# Audio.net
KiCad netlist of a schematic drawn in Altium Designer
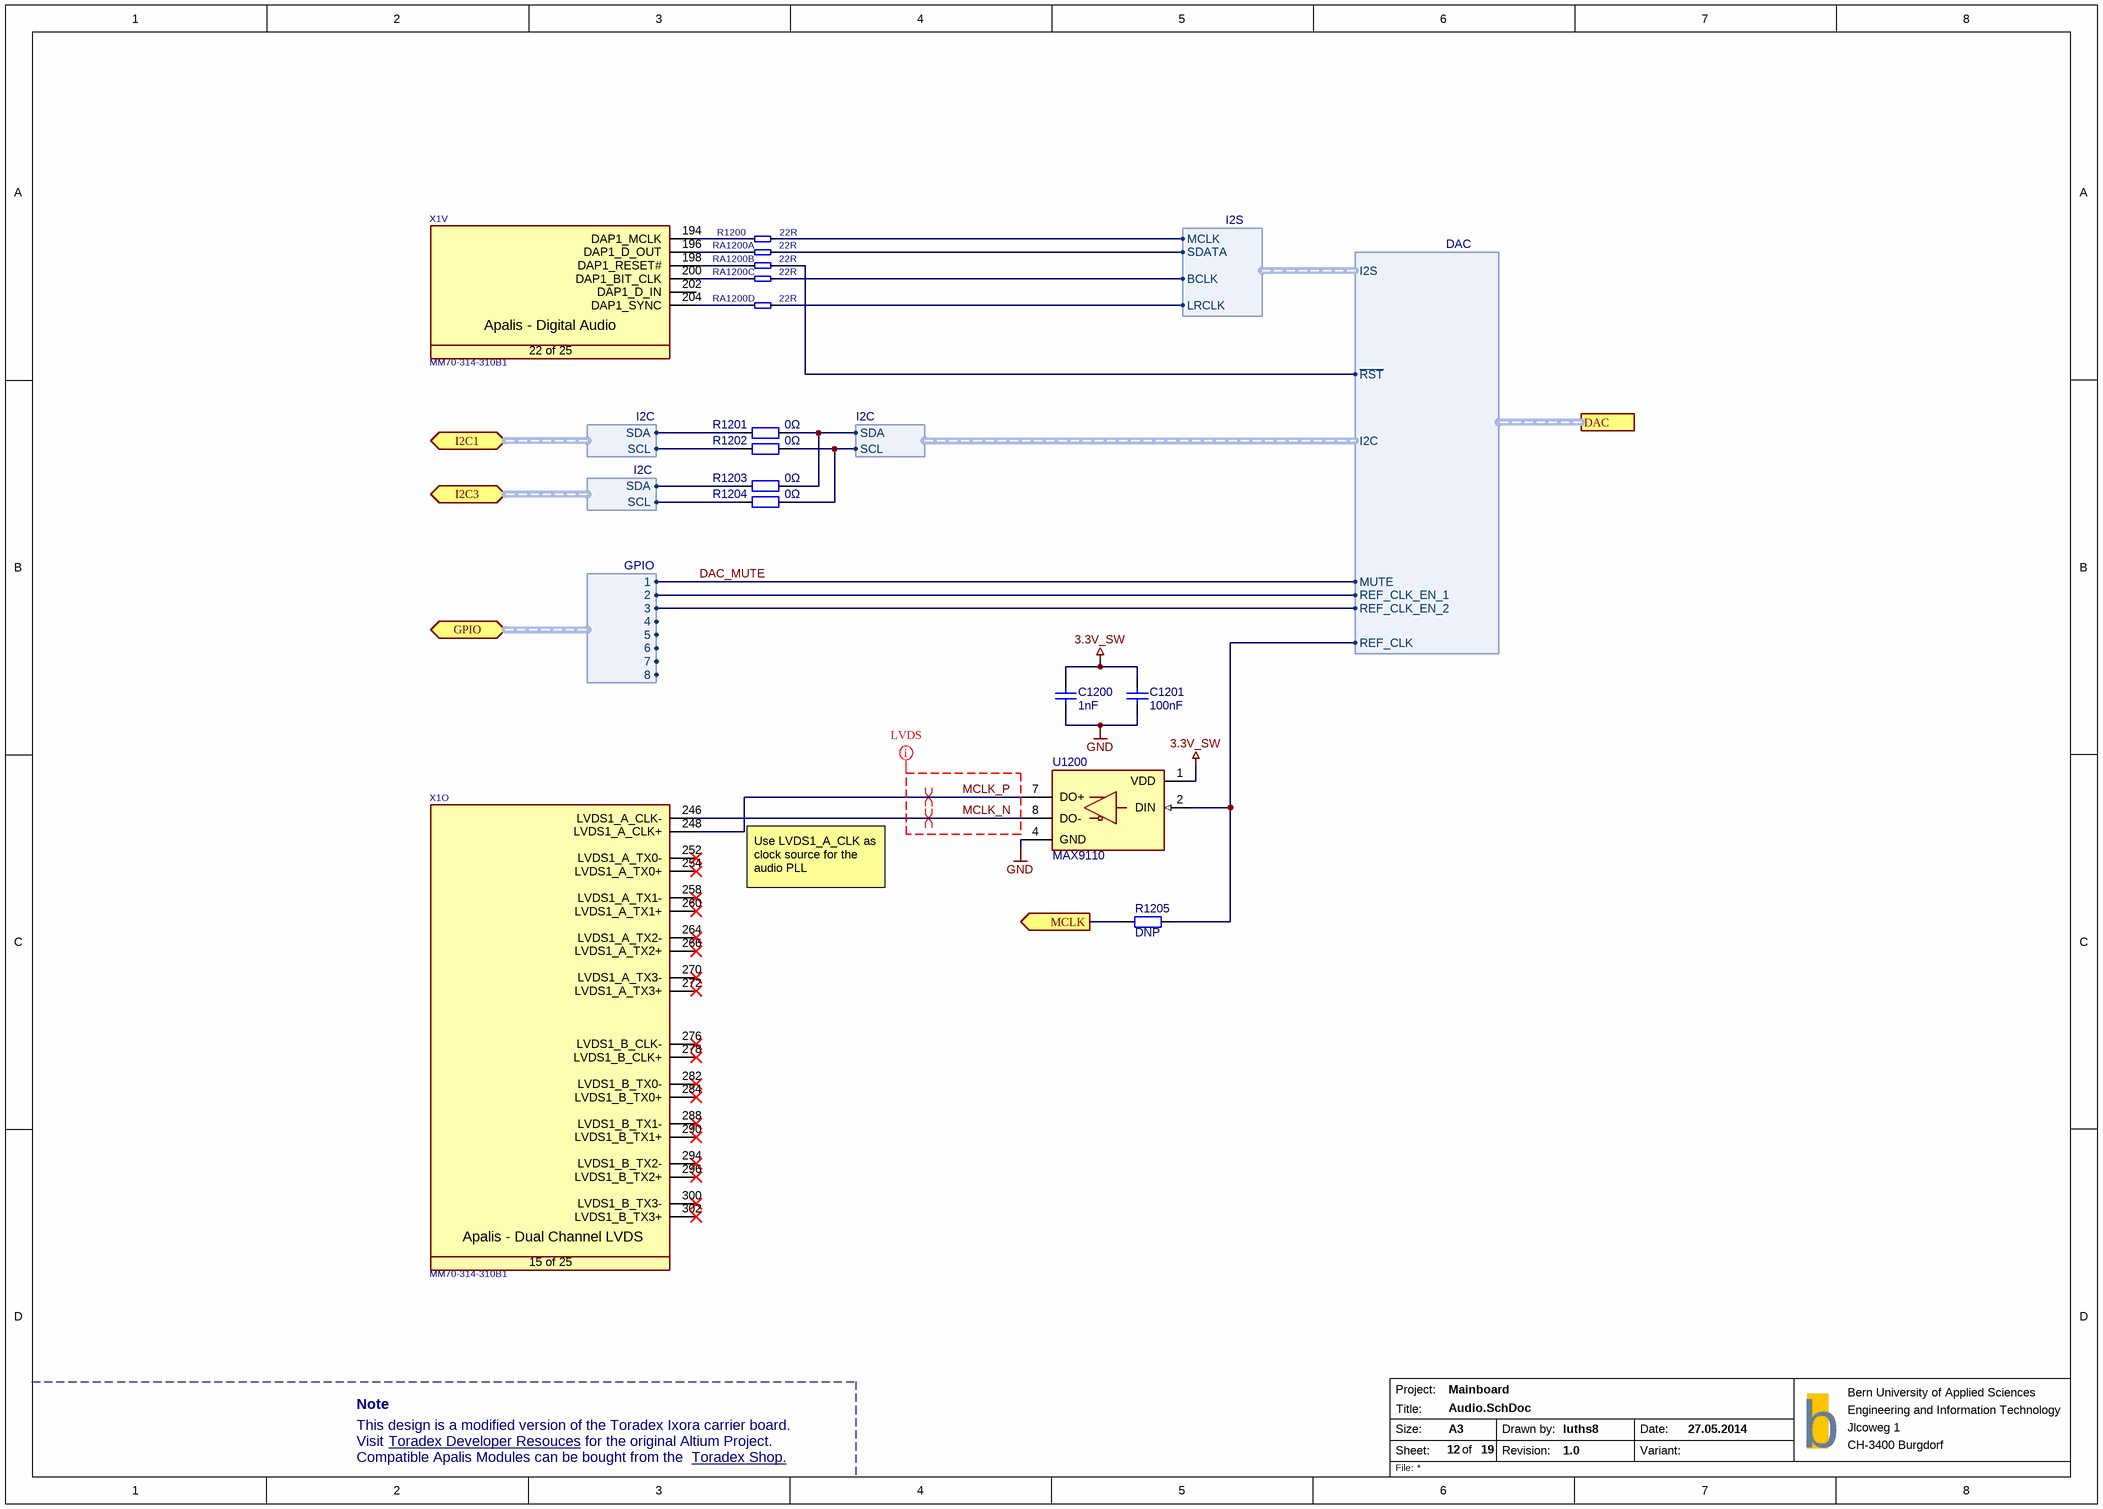
[diagram p0: Audio.SchDoc]

(export (version "E")
  (design (tool "Eeschema 10.0.6"))
  (components
    (comp (ref "C1200")
      (value "1nF")
      (footprint "SMD0603CAP")
      (description "Ceramic Capacitor")
      (libsource (lib "Audio-Streamer") (part "Capacitor Ceramic"))
    )
    (comp (ref "C1201")
      (value "100nF")
      (footprint "SMD0603CAP")
      (description "Ceramic Capacitor")
      (libsource (lib "Audio-Streamer") (part "Capacitor Ceramic"))
    )
    (comp (ref "R1200")
      (value "22R")
      (footprint "SMD0603RES")
      (description "Resistor 22 ohm 63mW 5% 0603")
      (fields (field (name "TOLERANCE") "5%"))
      (libsource (lib "Ixora") (part "R-22R-63mW-5%-0402"))
    )
    (comp (ref "R1201")
      (value "0Ω")
      (footprint "SMD0603RES")
      (description "Resistor")
      (libsource (lib "") (part "Resistor_1"))
    )
    (comp (ref "R1202")
      (value "0Ω")
      (footprint "SMD0603RES")
      (description "Resistor")
      (libsource (lib "") (part "Resistor_1"))
    )
    (comp (ref "R1203")
      (value "0Ω")
      (footprint "SMD0603RES")
      (description "Resistor")
      (libsource (lib "") (part "Resistor_1"))
    )
    (comp (ref "R1204")
      (value "0Ω")
      (footprint "SMD0603RES")
      (description "Resistor")
      (libsource (lib "") (part "Resistor_1"))
    )
    (comp (ref "R1205")
      (value "DNP")
      (footprint "SMD0603RES")
      (description "Resistor")
      (libsource (lib "Audio-Streamer") (part "Resistor"))
    )
    (comp (ref "RA1200")
      (value "22R")
      (footprint "T_Resistor_Array_X4")
      (description "Resistor Array 22 R 63mW 5% 1206")
      (fields (field (name "TOLERANCE") "5%"))
      (libsource (lib "Ixora") (part "RA-22R-63mW-5%-1206-div"))
    )
    (comp (ref "U1200")
      (value "MAX9110")
      (footprint "SOIC8")
      (description "LVDS Transmitter")
      (fields (field (name "MANUFACTURER PART NO.") "MAX9110ESA+"))
      (libsource (lib "Audio-Streamer") (part "MAX9110"))
    )
    (comp (ref "X1")
      (value "CON-JAE-MM70-314-310B1-314-0.5mm")
      (footprint "T_JAE_MM70-314-310B1")
      (description "MXM3 Connector")
      (fields (field (name "MANUFACTURER PART NO.") "MM70-314-310B1"))
      (libsource (lib "Ixora") (part "CON-JAE-MM70-314-310B1-314-0.5mm"))
    )
  )
  (nets
    (net (code "7") (name "/BCLK") (class "Default")
      (node (ref "RA1200") (pin "7") (pinfunction "7_7") (pintype "passive"))
    )
    (net (code "9") (name "/LRCLK") (class "Default")
      (node (ref "RA1200") (pin "8") (pinfunction "8_8") (pintype "passive"))
    )
    (net (code "10") (name "/MCLK") (class "Default")
      (node (ref "R1205") (pin "2") (pinfunction "2_2") (pintype "passive"))
    )
    (net (code "11") (name "/MCLK_N") (class "Default")
      (node (ref "U1200") (pin "8") (pinfunction "DO-_8") (pintype "passive"))
      (node (ref "X1") (pin "246") (pinfunction "LVDS1_A_CLK-_246") (pintype "passive"))
    )
    (net (code "12") (name "/MCLK_P") (class "Default")
      (node (ref "U1200") (pin "7") (pinfunction "DO+_7") (pintype "passive"))
      (node (ref "X1") (pin "248") (pinfunction "LVDS1_A_CLK+_248") (pintype "passive"))
    )
    (net (code "13") (name "/REF_CLK") (class "Default")
      (node (ref "R1205") (pin "1") (pinfunction "1_1") (pintype "passive"))
      (node (ref "U1200") (pin "2") (pinfunction "DIN_2") (pintype "input"))
    )
    (net (code "14") (name "/SDATA") (class "Default")
      (node (ref "RA1200") (pin "5") (pinfunction "5_5") (pintype "passive"))
    )
    (net (code "19") (name "/~{RST}") (class "Default")
      (node (ref "RA1200") (pin "6") (pinfunction "6_6") (pintype "passive"))
    )
    (net (code "20") (name "3.3V_SW") (class "Default")
      (node (ref "C1200") (pin "1") (pinfunction "1_1") (pintype "passive"))
      (node (ref "C1201") (pin "1") (pinfunction "1_1") (pintype "passive"))
      (node (ref "U1200") (pin "1") (pinfunction "VDD_1") (pintype "power_in"))
    )
    (net (code "21") (name "GND") (class "Default")
      (node (ref "C1200") (pin "2") (pinfunction "q_2") (pintype "passive"))
      (node (ref "C1201") (pin "2") (pinfunction "q_2") (pintype "passive"))
      (node (ref "U1200") (pin "4") (pinfunction "GND_4") (pintype "power_in"))
    )
    (net (code "22") (name "Net-(R1201-Pad1)") (class "Default")
      (node (ref "R1201") (pin "1") (pinfunction "1_1") (pintype "passive"))
      (node (ref "R1203") (pin "1") (pinfunction "1_1") (pintype "passive"))
    )
    (net (code "23") (name "Net-(R1202-Pad1)") (class "Default")
      (node (ref "R1202") (pin "1") (pinfunction "1_1") (pintype "passive"))
      (node (ref "R1204") (pin "1") (pinfunction "1_1") (pintype "passive"))
    )
    (net (code "24") (name "Net-(X1V-DAP1_BIT_CLK)") (class "Default")
      (node (ref "RA1200") (pin "3") (pinfunction "3_3") (pintype "passive"))
      (node (ref "X1") (pin "200") (pinfunction "DAP1_BIT_CLK_200") (pintype "passive"))
    )
    (net (code "25") (name "Net-(X1V-DAP1_D_OUT)") (class "Default")
      (node (ref "RA1200") (pin "1") (pinfunction "1_1") (pintype "passive"))
      (node (ref "X1") (pin "196") (pinfunction "DAP1_D_OUT_196") (pintype "passive"))
    )
    (net (code "26") (name "Net-(X1V-DAP1_MCLK)") (class "Default")
      (node (ref "R1200") (pin "1") (pinfunction "1_1") (pintype "passive"))
      (node (ref "X1") (pin "194") (pinfunction "DAP1_MCLK_194") (pintype "passive"))
    )
    (net (code "27") (name "Net-(X1V-DAP1_RESET#)") (class "Default")
      (node (ref "RA1200") (pin "2") (pinfunction "2_2") (pintype "passive"))
      (node (ref "X1") (pin "198") (pinfunction "DAP1_RESET#_198") (pintype "passive"))
    )
    (net (code "28") (name "Net-(X1V-DAP1_SYNC)") (class "Default")
      (node (ref "RA1200") (pin "4") (pinfunction "4_4") (pintype "passive"))
      (node (ref "X1") (pin "204") (pinfunction "DAP1_SYNC_204") (pintype "passive"))
    )
    (net (code "29") (name "unconnected-(R1200-Pad2)") (class "Default")
      (node (ref "R1200") (pin "2") (pinfunction "2_2") (pintype "passive"))
    )
    (net (code "30") (name "unconnected-(R1201-Pad2)") (class "Default")
      (node (ref "R1201") (pin "2") (pinfunction "2_2") (pintype "passive"))
    )
    (net (code "31") (name "unconnected-(R1202-Pad2)") (class "Default")
      (node (ref "R1202") (pin "2") (pinfunction "2_2") (pintype "passive"))
    )
    (net (code "32") (name "unconnected-(R1203-Pad2)") (class "Default")
      (node (ref "R1203") (pin "2") (pinfunction "2_2") (pintype "passive"))
    )
    (net (code "33") (name "unconnected-(R1204-Pad2)") (class "Default")
      (node (ref "R1204") (pin "2") (pinfunction "2_2") (pintype "passive"))
    )
    (net (code "34") (name "unconnected-(X1O-LVDS1_A_TX0+-Pad254)") (class "Default")
      (node (ref "X1") (pin "254") (pinfunction "LVDS1_A_TX0+_254") (pintype "passive+no_connect"))
    )
    (net (code "35") (name "unconnected-(X1O-LVDS1_A_TX0--Pad252)") (class "Default")
      (node (ref "X1") (pin "252") (pinfunction "LVDS1_A_TX0-_252") (pintype "passive+no_connect"))
    )
    (net (code "36") (name "unconnected-(X1O-LVDS1_A_TX1+-Pad260)") (class "Default")
      (node (ref "X1") (pin "260") (pinfunction "LVDS1_A_TX1+_260") (pintype "passive+no_connect"))
    )
    (net (code "37") (name "unconnected-(X1O-LVDS1_A_TX1--Pad258)") (class "Default")
      (node (ref "X1") (pin "258") (pinfunction "LVDS1_A_TX1-_258") (pintype "passive+no_connect"))
    )
    (net (code "38") (name "unconnected-(X1O-LVDS1_A_TX2+-Pad266)") (class "Default")
      (node (ref "X1") (pin "266") (pinfunction "LVDS1_A_TX2+_266") (pintype "passive+no_connect"))
    )
    (net (code "39") (name "unconnected-(X1O-LVDS1_A_TX2--Pad264)") (class "Default")
      (node (ref "X1") (pin "264") (pinfunction "LVDS1_A_TX2-_264") (pintype "passive+no_connect"))
    )
    (net (code "40") (name "unconnected-(X1O-LVDS1_A_TX3+-Pad272)") (class "Default")
      (node (ref "X1") (pin "272") (pinfunction "LVDS1_A_TX3+_272") (pintype "passive+no_connect"))
    )
    (net (code "41") (name "unconnected-(X1O-LVDS1_A_TX3--Pad270)") (class "Default")
      (node (ref "X1") (pin "270") (pinfunction "LVDS1_A_TX3-_270") (pintype "passive+no_connect"))
    )
    (net (code "42") (name "unconnected-(X1O-LVDS1_B_CLK+-Pad278)") (class "Default")
      (node (ref "X1") (pin "278") (pinfunction "LVDS1_B_CLK+_278") (pintype "passive+no_connect"))
    )
    (net (code "43") (name "unconnected-(X1O-LVDS1_B_CLK--Pad276)") (class "Default")
      (node (ref "X1") (pin "276") (pinfunction "LVDS1_B_CLK-_276") (pintype "passive+no_connect"))
    )
    (net (code "44") (name "unconnected-(X1O-LVDS1_B_TX0+-Pad284)") (class "Default")
      (node (ref "X1") (pin "284") (pinfunction "LVDS1_B_TX0+_284") (pintype "passive+no_connect"))
    )
    (net (code "45") (name "unconnected-(X1O-LVDS1_B_TX0--Pad282)") (class "Default")
      (node (ref "X1") (pin "282") (pinfunction "LVDS1_B_TX0-_282") (pintype "passive+no_connect"))
    )
    (net (code "46") (name "unconnected-(X1O-LVDS1_B_TX1+-Pad290)") (class "Default")
      (node (ref "X1") (pin "290") (pinfunction "LVDS1_B_TX1+_290") (pintype "passive+no_connect"))
    )
    (net (code "47") (name "unconnected-(X1O-LVDS1_B_TX1--Pad288)") (class "Default")
      (node (ref "X1") (pin "288") (pinfunction "LVDS1_B_TX1-_288") (pintype "passive+no_connect"))
    )
    (net (code "48") (name "unconnected-(X1O-LVDS1_B_TX2+-Pad296)") (class "Default")
      (node (ref "X1") (pin "296") (pinfunction "LVDS1_B_TX2+_296") (pintype "passive+no_connect"))
    )
    (net (code "49") (name "unconnected-(X1O-LVDS1_B_TX2--Pad294)") (class "Default")
      (node (ref "X1") (pin "294") (pinfunction "LVDS1_B_TX2-_294") (pintype "passive+no_connect"))
    )
    (net (code "50") (name "unconnected-(X1O-LVDS1_B_TX3+-Pad302)") (class "Default")
      (node (ref "X1") (pin "302") (pinfunction "LVDS1_B_TX3+_302") (pintype "passive+no_connect"))
    )
    (net (code "51") (name "unconnected-(X1O-LVDS1_B_TX3--Pad300)") (class "Default")
      (node (ref "X1") (pin "300") (pinfunction "LVDS1_B_TX3-_300") (pintype "passive+no_connect"))
    )
    (net (code "52") (name "unconnected-(X1V-DAP1_D_IN-Pad202)") (class "Default")
      (node (ref "X1") (pin "202") (pinfunction "DAP1_D_IN_202") (pintype "passive"))
    )
  )
)
